# USB2Serial.net
KiCad netlist of a schematic drawn in Altium Designer
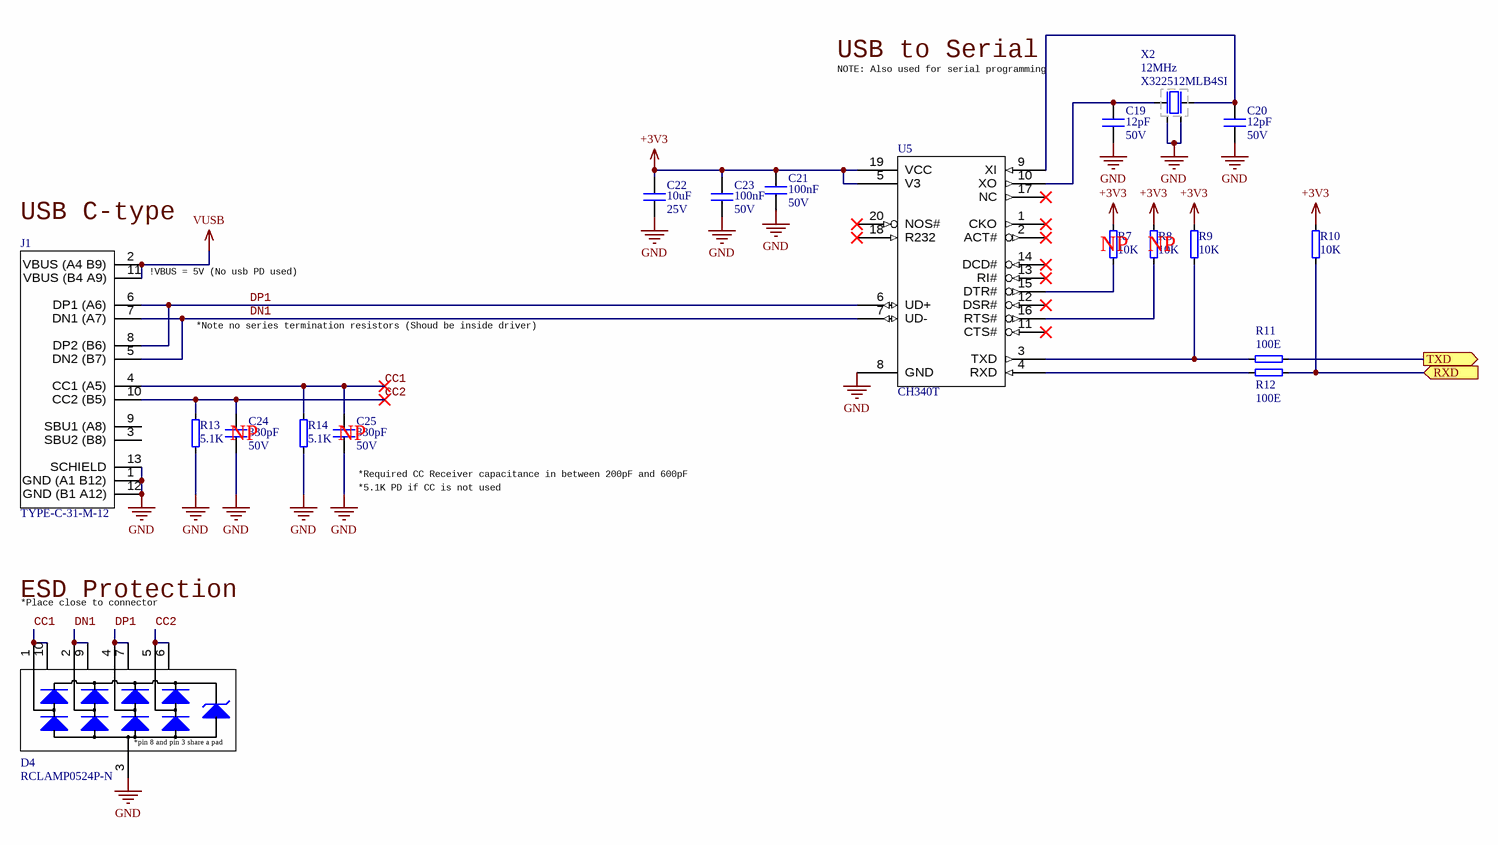
[diagram p0: USB2Serial.SchDoc]

(export (version "E")
  (design (tool "Eeschema 10.0.6"))
  (components
    (comp (ref "C19")
      (value "12pF")
      (footprint "CAP 0603 1608 IPC MEDIUM")
      (description "12pF ±5% 50V NP0 0603 Multilayer Ceramic Capacitors MLCC - SMD/SMT RoHS")
      (fields
        (field (name "VOLTAGE") "50V")
        (field (name "PART NUMBER") "CC0603JRNPO9BN120")
        (field (name "TOLERANCE") "5%")
      )
      (libsource (lib "P") (part "Capacitor"))
    )
    (comp (ref "C20")
      (value "12pF")
      (footprint "CAP 0603 1608 IPC MEDIUM")
      (description "12pF ±5% 50V NP0 0603 Multilayer Ceramic Capacitors MLCC - SMD/SMT RoHS")
      (fields
        (field (name "VOLTAGE") "50V")
        (field (name "PART NUMBER") "CC0603JRNPO9BN120")
        (field (name "TOLERANCE") "5%")
      )
      (libsource (lib "P") (part "Capacitor"))
    )
    (comp (ref "C21")
      (value "100nF")
      (footprint "CAP 0603 1608 IPC MEDIUM")
      (description "100nF ±10% 50V X7R 0603 Multilayer Ceramic Capacitors MLCC - SMD/SMT RoHS")
      (fields
        (field (name "VOLTAGE") "50V")
        (field (name "PART NUMBER") "C0603B104K500NT")
        (field (name "MANUFACTURER") "TORCH")
      )
      (libsource (lib "P") (part "Capacitor"))
    )
    (comp (ref "C22")
      (value "10uF")
      (footprint "CAP 1206 3216 IPC MEDIUM")
      (description "10uF ±10% 25V X5R 1206 Multilayer Ceramic Capacitors MLCC - SMD/SMT RoHS")
      (fields
        (field (name "VOLTAGE") "25V")
        (field (name "PART NUMBER") "CL31A106KAHNNNE")
        (field (name "TOLERANCE") "10%")
      )
      (libsource (lib "P") (part "Capacitor"))
    )
    (comp (ref "C23")
      (value "100nF")
      (footprint "CAP 0603 1608 IPC MEDIUM")
      (description "100nF ±10% 50V X7R 0603 Multilayer Ceramic Capacitors MLCC - SMD/SMT RoHS")
      (fields
        (field (name "VOLTAGE") "50V")
        (field (name "PART NUMBER") "C0603B104K500NT")
        (field (name "MANUFACTURER") "TORCH")
      )
      (libsource (lib "P") (part "Capacitor"))
    )
    (comp (ref "C24")
      (value "330pF")
      (footprint "CAP 0603 1608 IPC MEDIUM")
      (description "Generic 0603 1608 Capacitor")
      (fields
        (field (name "VOLTAGE") "50V")
        (field (name "PART NUMBER") "CL10C331JB8NNNC")
        (field (name "TOLERANCE") "5%")
      )
      (libsource (lib "P") (part "Capacitor"))
    )
    (comp (ref "C25")
      (value "330pF")
      (footprint "CAP 0603 1608 IPC MEDIUM")
      (description "Generic 0603 1608 Capacitor")
      (fields
        (field (name "VOLTAGE") "50V")
        (field (name "PART NUMBER") "CL10C331JB8NNNC")
        (field (name "TOLERANCE") "5%")
      )
      (libsource (lib "P") (part "Capacitor"))
    )
    (comp (ref "D4")
      (value "RCLAMP0524P-N")
      (footprint "RCLAMP0524P-N - BORN")
      (description "TVS ARRAY, 40W, 5V, UNIDIRECTIONAL, USB, HDMI")
      (fields (field (name "MANUFACTURER") "BORN"))
      (libsource (lib "P") (part "RCLAMP0524P-N - BORN"))
    )
    (comp (ref "J1")
      (value "TYPE-C-31-M-12")
      (footprint "TYPE-C-31-M-12 - KOREAN HROPARTS ELEC")
      (description "USB - Type C Female 12-pin")
      (fields (field (name "MANUFACTURER") "HRO ELECTRONICS"))
      (libsource (lib "P") (part "TYPE-C-31-M-12 - KOREAN HROPARTS ELEC"))
    )
    (comp (ref "R7")
      (value "10K")
      (footprint "RES 0603 1608 IPC MEDIUM")
      (description "10kΩ ±1% 0.1W ±100ppm/℃ 0603 Chip Resistor - Surface Mount RoHS")
      (fields (field (name "PART NUMBER") "RC0603FR-0710KL") (field (name "MANUFACTURER") "YAGEO"))
      (libsource (lib "P") (part "Resistor"))
    )
    (comp (ref "R8")
      (value "10K")
      (footprint "RES 0603 1608 IPC MEDIUM")
      (description "10kΩ ±1% 0.1W ±100ppm/℃ 0603 Chip Resistor - Surface Mount RoHS")
      (fields (field (name "PART NUMBER") "RC0603FR-0710KL") (field (name "MANUFACTURER") "YAGEO"))
      (libsource (lib "P") (part "Resistor"))
    )
    (comp (ref "R9")
      (value "10K")
      (footprint "RES 0603 1608 IPC MEDIUM")
      (description "10kΩ ±1% 0.1W ±100ppm/℃ 0603 Chip Resistor - Surface Mount RoHS")
      (fields (field (name "PART NUMBER") "RC0603FR-0710KL") (field (name "MANUFACTURER") "YAGEO"))
      (libsource (lib "P") (part "Resistor"))
    )
    (comp (ref "R10")
      (value "10K")
      (footprint "RES 0603 1608 IPC MEDIUM")
      (description "10kΩ ±1% 0.1W ±100ppm/℃ 0603 Chip Resistor - Surface Mount RoHS")
      (fields (field (name "PART NUMBER") "RC0603FR-0710KL") (field (name "MANUFACTURER") "YAGEO"))
      (libsource (lib "P") (part "Resistor"))
    )
    (comp (ref "R11")
      (value "100E")
      (footprint "RES 0603 1608 IPC MEDIUM")
      (fields
        (field (name "PART NUMBER") "RC0603FR-07100RL")
        (field (name "VOLTAGE") "75V")
        (field (name "POWER") "100mW")
      )
      (libsource (lib "") (part "Resistor_1"))
    )
    (comp (ref "R12")
      (value "100E")
      (footprint "RES 0603 1608 IPC MEDIUM")
      (fields
        (field (name "PART NUMBER") "RC0603FR-07100RL")
        (field (name "VOLTAGE") "75V")
        (field (name "POWER") "100mW")
      )
      (libsource (lib "") (part "Resistor_1"))
    )
    (comp (ref "R13")
      (value "5.1K")
      (footprint "RES 0603 1608 IPC MEDIUM")
      (description "5.1kΩ ±1% 0.1W 0603 Chip Resistor - Surface Mount RoHS")
      (fields (field (name "PART NUMBER") "RMC06035.1K1%N") (field (name "VOLTAGE") "50V"))
      (libsource (lib "P") (part "Resistor"))
    )
    (comp (ref "R14")
      (value "5.1K")
      (footprint "RES 0603 1608 IPC MEDIUM")
      (description "5.1kΩ ±1% 0.1W 0603 Chip Resistor - Surface Mount RoHS")
      (fields (field (name "PART NUMBER") "RMC06035.1K1%N") (field (name "VOLTAGE") "50V"))
      (libsource (lib "P") (part "Resistor"))
    )
    (comp (ref "U5")
      (value "CH340T")
      (footprint "CH340T - WCH")
      (description "USB to UART Bridge Controller USB 2.0 Full speed 50bps to 2Mbps")
      (fields (field (name "MANUFACTURER") "WCH"))
      (libsource (lib "P") (part "CH340T - WCH"))
    )
    (comp (ref "X2")
      (value "X322512MLB4SI")
      (footprint "X322512MLB4SI - YXC")
      (description "12MHz ±10ppm 9pF 80Ω SMD-3225_4P Crystals RoHS")
      (fields (field (name "FREQUENCY") "12MHz") (field (name "MANUFACTURER") "YXC"))
      (libsource (lib "P") (part "Crystal in1 gnd2 out3 gnd4"))
    )
  )
  (nets
    (net (code "1") (name "+3V3") (class "Default")
      (node (ref "C21") (pin "1") (pinfunction "1_1") (pintype "passive"))
      (node (ref "C22") (pin "1") (pinfunction "1_1") (pintype "passive"))
      (node (ref "C23") (pin "1") (pinfunction "1_1") (pintype "passive"))
      (node (ref "R10") (pin "1") (pinfunction "1_1") (pintype "passive"))
      (node (ref "R7") (pin "1") (pinfunction "1_1") (pintype "passive"))
      (node (ref "R8") (pin "1") (pinfunction "1_1") (pintype "passive"))
      (node (ref "R9") (pin "1") (pinfunction "1_1") (pintype "passive"))
      (node (ref "U5") (pin "19") (pinfunction "VCC_19") (pintype "power_in"))
      (node (ref "U5") (pin "5") (pinfunction "V3_5") (pintype "power_in"))
    )
    (net (code "2") (name "/CC1") (class "Default")
      (node (ref "C25") (pin "1") (pinfunction "1_1") (pintype "passive"))
      (node (ref "D4") (pin "1") (pintype "passive"))
      (node (ref "D4") (pin "10") (pinfunction "NC_10") (pintype "passive"))
      (node (ref "J1") (pin "4") (pinfunction "CC1_(A5)_4") (pintype "passive"))
      (node (ref "R14") (pin "1") (pinfunction "1_1") (pintype "passive"))
    )
    (net (code "3") (name "/CC2") (class "Default")
      (node (ref "C24") (pin "1") (pinfunction "1_1") (pintype "passive"))
      (node (ref "D4") (pin "5") (pintype "passive"))
      (node (ref "D4") (pin "6") (pinfunction "NC_6") (pintype "passive"))
      (node (ref "J1") (pin "10") (pinfunction "CC2_(B5)_10") (pintype "passive"))
      (node (ref "R13") (pin "1") (pinfunction "1_1") (pintype "passive"))
    )
    (net (code "4") (name "/DN1") (class "Default")
      (node (ref "D4") (pin "2") (pintype "passive"))
      (node (ref "D4") (pin "9") (pinfunction "NC_9") (pintype "passive"))
      (node (ref "J1") (pin "5") (pinfunction "DN2_(B7)_5") (pintype "passive"))
      (node (ref "J1") (pin "7") (pinfunction "DN1_(A7)_7") (pintype "passive"))
      (node (ref "U5") (pin "7") (pinfunction "UD-_7") (pintype "bidirectional"))
    )
    (net (code "5") (name "/DP1") (class "Default")
      (node (ref "D4") (pin "4") (pintype "passive"))
      (node (ref "D4") (pin "7") (pinfunction "NC_7") (pintype "passive"))
      (node (ref "J1") (pin "6") (pinfunction "DP1_(A6)_6") (pintype "passive"))
      (node (ref "J1") (pin "8") (pinfunction "DP2_(B6)_8") (pintype "passive"))
      (node (ref "U5") (pin "6") (pinfunction "UD+_6") (pintype "bidirectional"))
    )
    (net (code "6") (name "/RXD") (class "Default")
      (node (ref "R10") (pin "2") (pinfunction "2_2") (pintype "passive"))
      (node (ref "R12") (pin "2") (pinfunction "2_2") (pintype "passive"))
    )
    (net (code "7") (name "/TXD") (class "Default")
      (node (ref "R11") (pin "2") (pinfunction "2_2") (pintype "passive"))
    )
    (net (code "8") (name "GND") (class "Default")
      (node (ref "C19") (pin "2") (pinfunction "2_2") (pintype "passive"))
      (node (ref "C20") (pin "2") (pinfunction "2_2") (pintype "passive"))
      (node (ref "C21") (pin "2") (pinfunction "2_2") (pintype "passive"))
      (node (ref "C22") (pin "2") (pinfunction "2_2") (pintype "passive"))
      (node (ref "C23") (pin "2") (pinfunction "2_2") (pintype "passive"))
      (node (ref "C24") (pin "2") (pinfunction "2_2") (pintype "passive"))
      (node (ref "C25") (pin "2") (pinfunction "2_2") (pintype "passive"))
      (node (ref "D4") (pin "3") (pinfunction "3_8_3") (pintype "power_in"))
      (node (ref "J1") (pin "1") (pinfunction "GND_(A1_B12)_1") (pintype "passive"))
      (node (ref "J1") (pin "12") (pinfunction "GND_(B1_A12)_12") (pintype "passive"))
      (node (ref "J1") (pin "13") (pinfunction "SCHIELD_13") (pintype "passive"))
      (node (ref "R13") (pin "2") (pinfunction "2_2") (pintype "passive"))
      (node (ref "R14") (pin "2") (pinfunction "2_2") (pintype "passive"))
      (node (ref "U5") (pin "8") (pinfunction "GND_8") (pintype "power_in"))
      (node (ref "X2") (pin "2") (pinfunction "GND_2") (pintype "passive"))
      (node (ref "X2") (pin "4") (pinfunction "GND_4") (pintype "passive"))
    )
    (net (code "9") (name "Net-(U5-DTR#)") (class "Default")
      (node (ref "R7") (pin "2") (pinfunction "2_2") (pintype "passive"))
      (node (ref "U5") (pin "15") (pinfunction "DTR#_15") (pintype "output"))
    )
    (net (code "10") (name "Net-(U5-RTS#)") (class "Default")
      (node (ref "R8") (pin "2") (pinfunction "2_2") (pintype "passive"))
      (node (ref "U5") (pin "16") (pinfunction "RTS#_16") (pintype "output"))
    )
    (net (code "11") (name "Net-(U5-RXD)") (class "Default")
      (node (ref "R12") (pin "1") (pinfunction "1_1") (pintype "passive"))
      (node (ref "U5") (pin "4") (pinfunction "RXD_4") (pintype "input"))
    )
    (net (code "12") (name "Net-(U5-TXD)") (class "Default")
      (node (ref "R11") (pin "1") (pinfunction "1_1") (pintype "passive"))
      (node (ref "R9") (pin "2") (pinfunction "2_2") (pintype "passive"))
      (node (ref "U5") (pin "3") (pinfunction "TXD_3") (pintype "output"))
    )
    (net (code "13") (name "Net-(U5-XI)") (class "Default")
      (node (ref "C20") (pin "1") (pinfunction "1_1") (pintype "passive"))
      (node (ref "U5") (pin "9") (pinfunction "XI_9") (pintype "input"))
      (node (ref "X2") (pin "1") (pinfunction "in_1") (pintype "passive"))
    )
    (net (code "14") (name "Net-(U5-XO)") (class "Default")
      (node (ref "C19") (pin "1") (pinfunction "1_1") (pintype "passive"))
      (node (ref "U5") (pin "10") (pinfunction "XO_10") (pintype "output"))
      (node (ref "X2") (pin "3") (pinfunction "out_3") (pintype "passive"))
    )
    (net (code "15") (name "VUSB") (class "Default")
      (node (ref "J1") (pin "11") (pinfunction "VBUS_(B4_A9)_11") (pintype "passive"))
      (node (ref "J1") (pin "2") (pinfunction "VBUS_(A4_B9)_2") (pintype "passive"))
    )
    (net (code "16") (name "unconnected-(J1-SBU1_(A8)-Pad9)") (class "Default")
      (node (ref "J1") (pin "9") (pinfunction "SBU1_(A8)_9") (pintype "passive"))
    )
    (net (code "17") (name "unconnected-(J1-SBU2_(B8)-Pad3)") (class "Default")
      (node (ref "J1") (pin "3") (pinfunction "SBU2_(B8)_3") (pintype "passive"))
    )
    (net (code "18") (name "unconnected-(U5-ACT#-Pad2)") (class "Default")
      (node (ref "U5") (pin "2") (pinfunction "ACT#_2") (pintype "output+no_connect"))
    )
    (net (code "19") (name "unconnected-(U5-CKO-Pad1)") (class "Default")
      (node (ref "U5") (pin "1") (pinfunction "CKO_1") (pintype "output+no_connect"))
    )
    (net (code "20") (name "unconnected-(U5-CTS#-Pad11)") (class "Default")
      (node (ref "U5") (pin "11") (pinfunction "CTS#_11") (pintype "input+no_connect"))
    )
    (net (code "21") (name "unconnected-(U5-DCD#-Pad14)") (class "Default")
      (node (ref "U5") (pin "14") (pinfunction "DCD#_14") (pintype "input+no_connect"))
    )
    (net (code "22") (name "unconnected-(U5-DSR#-Pad12)") (class "Default")
      (node (ref "U5") (pin "12") (pinfunction "DSR#_12") (pintype "input+no_connect"))
    )
    (net (code "23") (name "unconnected-(U5-NC-Pad17)") (class "Default")
      (node (ref "U5") (pin "17") (pinfunction "NC_17") (pintype "output+no_connect"))
    )
    (net (code "24") (name "unconnected-(U5-NOS#-Pad20)") (class "Default")
      (node (ref "U5") (pin "20") (pinfunction "NOS#_20") (pintype "input+no_connect"))
    )
    (net (code "25") (name "unconnected-(U5-R232-Pad18)") (class "Default")
      (node (ref "U5") (pin "18") (pinfunction "R232_18") (pintype "input+no_connect"))
    )
    (net (code "26") (name "unconnected-(U5-RI#-Pad13)") (class "Default")
      (node (ref "U5") (pin "13") (pinfunction "RI#_13") (pintype "input+no_connect"))
    )
  )
)
